# RM-USB.net
KiCad netlist of a schematic drawn in EAGLE
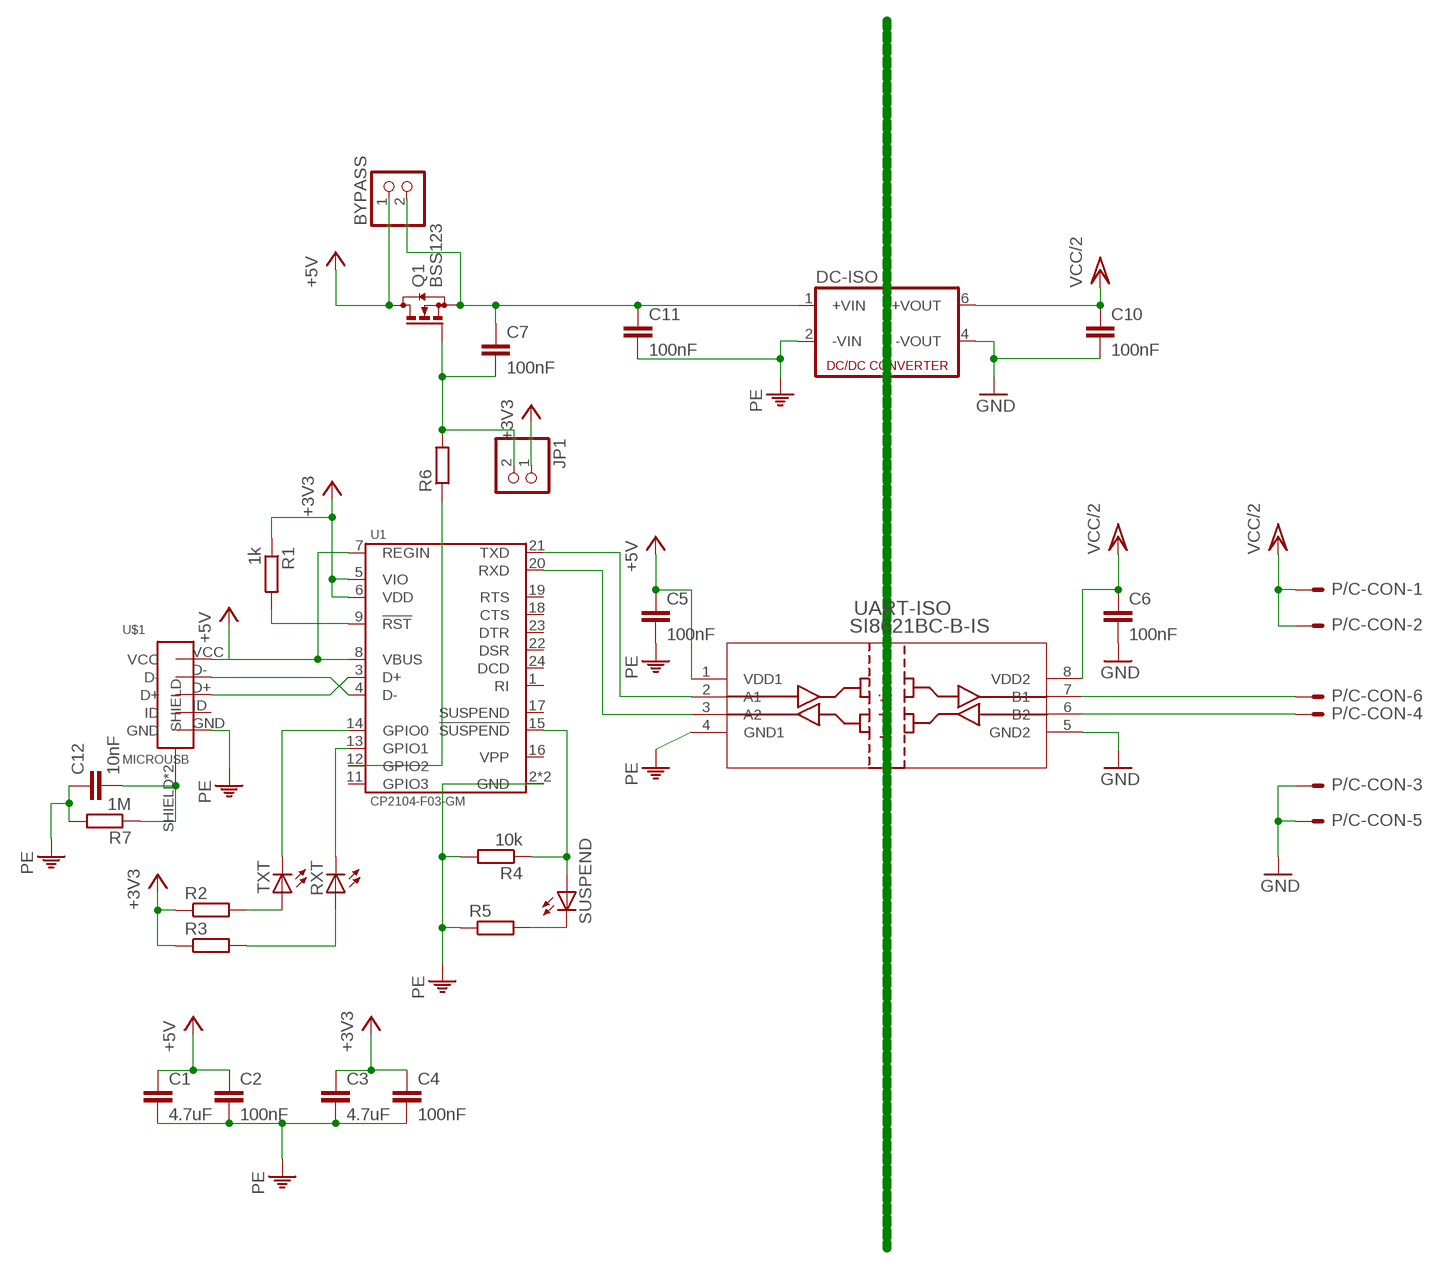
[diagram p0: schematic, sheet 1]

(export (version "E")
  (design (tool "Eeschema 10.0.6"))
  (components
    (comp (ref "BYPASS")
      (value "PINHD-1X2")
      (footprint "eagle-import:1X02")
      (libsource (lib "eagle-import") (part "PINHD-1X2"))
    )
    (comp (ref "C1")
      (value "4.7uF")
      (footprint "eagle-import:C1206K")
      (libsource (lib "eagle-import") (part "C-EUC1206K"))
    )
    (comp (ref "C2")
      (value "100nF")
      (footprint "eagle-import:C0603")
      (libsource (lib "eagle-import") (part "C-EUC0603"))
    )
    (comp (ref "C3")
      (value "4.7uF")
      (footprint "eagle-import:C1206K")
      (libsource (lib "eagle-import") (part "C-EUC1206K"))
    )
    (comp (ref "C4")
      (value "100nF")
      (footprint "eagle-import:C0603")
      (libsource (lib "eagle-import") (part "C-EUC0603"))
    )
    (comp (ref "C5")
      (value "100nF")
      (footprint "eagle-import:C0603")
      (libsource (lib "eagle-import") (part "C-EUC0603"))
    )
    (comp (ref "C6")
      (value "100nF")
      (footprint "eagle-import:C0603")
      (libsource (lib "eagle-import") (part "C-EUC0603"))
    )
    (comp (ref "C7")
      (value "100nF")
      (footprint "eagle-import:C0603")
      (libsource (lib "eagle-import") (part "C-EUC0603"))
    )
    (comp (ref "C10")
      (value "100nF")
      (footprint "eagle-import:C0603")
      (libsource (lib "eagle-import") (part "C-EUC0603"))
    )
    (comp (ref "C11")
      (value "100nF")
      (footprint "eagle-import:C0603")
      (libsource (lib "eagle-import") (part "C-EUC0603"))
    )
    (comp (ref "C12")
      (value "10nF")
      (footprint "eagle-import:C0603")
      (libsource (lib "eagle-import") (part "C-EUC0603"))
    )
    (comp (ref "DC-ISO")
      (value "NMA")
      (footprint "eagle-import:NMA")
      (libsource (lib "eagle-import") (part "NMA"))
    )
    (comp (ref "JP1")
      (value "PINHD-1X2")
      (footprint "eagle-import:1X02")
      (libsource (lib "eagle-import") (part "PINHD-1X2"))
    )
    (comp (ref "P/C-CON")
      (value "ML6EL")
      (footprint "eagle-import:ML6L")
      (libsource (lib "eagle-import") (part "ML6EL"))
    )
    (comp (ref "Q1")
      (value "BSS123")
      (footprint "eagle-import:SOT23")
      (libsource (lib "eagle-import") (part "BSS123"))
    )
    (comp (ref "R1")
      (value "1k")
      (footprint "eagle-import:R0603")
      (libsource (lib "eagle-import") (part "R-EU_R0603"))
    )
    (comp (ref "R2")
      (value "R-EU_R0603")
      (footprint "eagle-import:R0603")
      (libsource (lib "eagle-import") (part "R-EU_R0603"))
    )
    (comp (ref "R3")
      (value "R-EU_R0603")
      (footprint "eagle-import:R0603")
      (libsource (lib "eagle-import") (part "R-EU_R0603"))
    )
    (comp (ref "R4")
      (value "10k")
      (footprint "eagle-import:R0603")
      (libsource (lib "eagle-import") (part "R-EU_R0603"))
    )
    (comp (ref "R5")
      (value "R-EU_R0603")
      (footprint "eagle-import:R0603")
      (libsource (lib "eagle-import") (part "R-EU_R0603"))
    )
    (comp (ref "R6")
      (value "R-EU_R0603")
      (footprint "eagle-import:R0603")
      (libsource (lib "eagle-import") (part "R-EU_R0603"))
    )
    (comp (ref "R7")
      (value "1M")
      (footprint "eagle-import:R0603")
      (libsource (lib "eagle-import") (part "R-EU_R0603"))
    )
    (comp (ref "RXT")
      (value "LED3MM")
      (footprint "eagle-import:LED3MM")
      (libsource (lib "eagle-import") (part "LED3MM"))
    )
    (comp (ref "SUSPEND")
      (value "LED3MM")
      (footprint "eagle-import:LED3MM")
      (libsource (lib "eagle-import") (part "LED3MM"))
    )
    (comp (ref "TXT")
      (value "LED3MM")
      (footprint "eagle-import:LED3MM")
      (libsource (lib "eagle-import") (part "LED3MM"))
    )
    (comp (ref "U$1")
      (value "MICROUSB")
      (footprint "eagle-import:MICROUSB")
      (libsource (lib "eagle-import") (part "MICROUSB"))
    )
    (comp (ref "U1")
      (value "CP2104-F03-GM")
      (footprint "eagle-import:QFN-24-4X4")
      (libsource (lib "eagle-import") (part "CP2104-F03-GM"))
    )
    (comp (ref "UART-ISO")
      (value "SI8621BC-B-IS")
      (footprint "eagle-import:SOIC-8")
      (libsource (lib "eagle-import") (part "SI8621BC-B-IS"))
    )
  )
  (nets
    (net (code "1") (name "+3V3") (class "Default")
      (node (ref "C3") (pin "1") (pinfunction "1_1") (pintype "passive"))
      (node (ref "C4") (pin "1") (pinfunction "1_1") (pintype "passive"))
      (node (ref "JP1") (pin "1") (pinfunction "1_1") (pintype "passive"))
      (node (ref "R1") (pin "1") (pinfunction "1_1") (pintype "passive"))
      (node (ref "R2") (pin "1") (pinfunction "1_1") (pintype "passive"))
      (node (ref "R3") (pin "1") (pinfunction "1_1") (pintype "passive"))
      (node (ref "U1") (pin "5") (pinfunction "VIO_5") (pintype "bidirectional"))
      (node (ref "U1") (pin "6") (pinfunction "VDD_6") (pintype "bidirectional"))
    )
    (net (code "2") (name "+5V") (class "Default")
      (node (ref "BYPASS") (pin "1") (pinfunction "1_1") (pintype "passive"))
      (node (ref "C1") (pin "1") (pinfunction "1_1") (pintype "passive"))
      (node (ref "C2") (pin "1") (pinfunction "1_1") (pintype "passive"))
      (node (ref "C5") (pin "1") (pinfunction "1_1") (pintype "passive"))
      (node (ref "Q1") (pin "3") (pinfunction "D_3") (pintype "passive"))
      (node (ref "U$1") (pin "VCC") (pinfunction "VCC_VCC") (pintype "bidirectional"))
      (node (ref "U1") (pin "7") (pinfunction "REGIN_7") (pintype "bidirectional"))
      (node (ref "U1") (pin "8") (pinfunction "VBUS_8") (pintype "bidirectional"))
      (node (ref "UART-ISO") (pin "1") (pinfunction "VDD1_1") (pintype "passive"))
    )
    (net (code "3") (name "GND") (class "Default")
      (node (ref "C10") (pin "2") (pinfunction "2_2") (pintype "passive"))
      (node (ref "C6") (pin "2") (pinfunction "2_2") (pintype "passive"))
      (node (ref "DC-ISO") (pin "4") (pinfunction "-VOUT_4") (pintype "passive"))
      (node (ref "P/C-CON") (pin "3") (pinfunction "S_3") (pintype "passive"))
      (node (ref "P/C-CON") (pin "5") (pinfunction "S_5") (pintype "passive"))
      (node (ref "UART-ISO") (pin "5") (pinfunction "GND2_5") (pintype "passive"))
    )
    (net (code "4") (name "Net-(C12-Pad2)") (class "Default")
      (node (ref "C12") (pin "2") (pinfunction "2_2") (pintype "passive"))
      (node (ref "R7") (pin "1") (pinfunction "1_1") (pintype "passive"))
      (node (ref "U$1") (pin "SHIELD") (pinfunction "SHIELD_SHIELD") (pintype "bidirectional"))
      (node (ref "U$1") (pin "SHIELD1") (pinfunction "SHIELD_SHIELD1") (pintype "bidirectional"))
    )
    (net (code "5") (name "Net-(DC-ISO-+VIN)") (class "Default")
      (node (ref "BYPASS") (pin "2") (pinfunction "2_2") (pintype "passive"))
      (node (ref "C11") (pin "1") (pinfunction "1_1") (pintype "passive"))
      (node (ref "C7") (pin "1") (pinfunction "1_1") (pintype "passive"))
      (node (ref "DC-ISO") (pin "1") (pinfunction "+VIN_1") (pintype "passive"))
      (node (ref "Q1") (pin "2") (pinfunction "S_2") (pintype "passive"))
    )
    (net (code "6") (name "Net-(P/C-COND-S)") (class "Default")
      (node (ref "P/C-CON") (pin "4") (pinfunction "S_4") (pintype "passive"))
      (node (ref "UART-ISO") (pin "6") (pinfunction "B2_6") (pintype "input"))
    )
    (net (code "7") (name "Net-(P/C-CONF-S)") (class "Default")
      (node (ref "P/C-CON") (pin "6") (pinfunction "S_6") (pintype "passive"))
      (node (ref "UART-ISO") (pin "7") (pinfunction "B1_7") (pintype "output"))
    )
    (net (code "8") (name "Net-(Q1-G)") (class "Default")
      (node (ref "C7") (pin "2") (pinfunction "2_2") (pintype "passive"))
      (node (ref "JP1") (pin "2") (pinfunction "2_2") (pintype "passive"))
      (node (ref "Q1") (pin "1") (pinfunction "G_1") (pintype "passive"))
      (node (ref "R6") (pin "2") (pinfunction "2_2") (pintype "passive"))
    )
    (net (code "9") (name "Net-(R2-Pad2)") (class "Default")
      (node (ref "R2") (pin "2") (pinfunction "2_2") (pintype "passive"))
      (node (ref "TXT") (pin "A") (pinfunction "A_A") (pintype "passive"))
    )
    (net (code "10") (name "Net-(R3-Pad2)") (class "Default")
      (node (ref "R3") (pin "2") (pinfunction "2_2") (pintype "passive"))
      (node (ref "RXT") (pin "A") (pinfunction "A_A") (pintype "passive"))
    )
    (net (code "11") (name "Net-(RXT-C)") (class "Default")
      (node (ref "RXT") (pin "K") (pinfunction "C_K") (pintype "passive"))
      (node (ref "U1") (pin "13") (pinfunction "GPIO1_13") (pintype "bidirectional"))
    )
    (net (code "12") (name "Net-(SUSPEND-C)") (class "Default")
      (node (ref "R5") (pin "2") (pinfunction "2_2") (pintype "passive"))
      (node (ref "SUSPEND") (pin "K") (pinfunction "C_K") (pintype "passive"))
    )
    (net (code "13") (name "Net-(TXT-C)") (class "Default")
      (node (ref "TXT") (pin "K") (pinfunction "C_K") (pintype "passive"))
      (node (ref "U1") (pin "14") (pinfunction "GPIO0_14") (pintype "bidirectional"))
    )
    (net (code "14") (name "Net-(U1-D+)") (class "Default")
      (node (ref "U$1") (pin "D+") (pinfunction "D+_D+") (pintype "bidirectional"))
      (node (ref "U1") (pin "3") (pinfunction "D+_3") (pintype "bidirectional"))
    )
    (net (code "15") (name "Net-(U1-D-)") (class "Default")
      (node (ref "U$1") (pin "D-") (pinfunction "D-_D-") (pintype "bidirectional"))
      (node (ref "U1") (pin "4") (pinfunction "D-_4") (pintype "bidirectional"))
    )
    (net (code "16") (name "Net-(U1-GPIO2)") (class "Default")
      (node (ref "R6") (pin "1") (pinfunction "1_1") (pintype "passive"))
      (node (ref "U1") (pin "12") (pinfunction "GPIO2_12") (pintype "bidirectional"))
    )
    (net (code "17") (name "Net-(U1-RXD)") (class "Default")
      (node (ref "U1") (pin "20") (pinfunction "RXD_20") (pintype "bidirectional"))
      (node (ref "UART-ISO") (pin "3") (pinfunction "A2_3") (pintype "output"))
    )
    (net (code "18") (name "Net-(U1-TXD)") (class "Default")
      (node (ref "U1") (pin "21") (pinfunction "TXD_21") (pintype "bidirectional"))
      (node (ref "UART-ISO") (pin "2") (pinfunction "A1_2") (pintype "input"))
    )
    (net (code "19") (name "Net-(U1-~{RST})") (class "Default")
      (node (ref "R1") (pin "2") (pinfunction "2_2") (pintype "passive"))
      (node (ref "U1") (pin "9") (pinfunction "~{RST}_9") (pintype "bidirectional"))
    )
    (net (code "20") (name "Net-(U1-~{SUSPEND})") (class "Default")
      (node (ref "R4") (pin "1") (pinfunction "1_1") (pintype "passive"))
      (node (ref "SUSPEND") (pin "A") (pinfunction "A_A") (pintype "passive"))
      (node (ref "U1") (pin "15") (pinfunction "~{SUSPEND}_15") (pintype "bidirectional"))
    )
    (net (code "21") (name "PE") (class "Default")
      (node (ref "C1") (pin "2") (pinfunction "2_2") (pintype "passive"))
      (node (ref "C11") (pin "2") (pinfunction "2_2") (pintype "passive"))
      (node (ref "C12") (pin "1") (pinfunction "1_1") (pintype "passive"))
      (node (ref "C2") (pin "2") (pinfunction "2_2") (pintype "passive"))
      (node (ref "C3") (pin "2") (pinfunction "2_2") (pintype "passive"))
      (node (ref "C4") (pin "2") (pinfunction "2_2") (pintype "passive"))
      (node (ref "C5") (pin "2") (pinfunction "2_2") (pintype "passive"))
      (node (ref "DC-ISO") (pin "2") (pinfunction "-VIN_2") (pintype "passive"))
      (node (ref "R4") (pin "2") (pinfunction "2_2") (pintype "passive"))
      (node (ref "R5") (pin "1") (pinfunction "1_1") (pintype "passive"))
      (node (ref "R7") (pin "2") (pinfunction "2_2") (pintype "passive"))
      (node (ref "U$1") (pin "GND") (pinfunction "GND_GND") (pintype "bidirectional"))
      (node (ref "U1") (pin "2") (pinfunction "GND_2") (pintype "bidirectional"))
      (node (ref "U1") (pin "PAD") (pinfunction "GND_PAD") (pintype "bidirectional"))
      (node (ref "UART-ISO") (pin "4") (pinfunction "GND1_4") (pintype "passive"))
    )
    (net (code "22") (name "VCC{slash}2") (class "Default")
      (node (ref "C10") (pin "1") (pinfunction "1_1") (pintype "passive"))
      (node (ref "C6") (pin "1") (pinfunction "1_1") (pintype "passive"))
      (node (ref "DC-ISO") (pin "6") (pinfunction "+VOUT_6") (pintype "passive"))
      (node (ref "P/C-CON") (pin "1") (pinfunction "S_1") (pintype "passive"))
      (node (ref "P/C-CON") (pin "2") (pinfunction "S_2") (pintype "passive"))
      (node (ref "UART-ISO") (pin "8") (pinfunction "VDD2_8") (pintype "passive"))
    )
    (net (code "23") (name "unconnected-(U$1-PadID)") (class "Default")
      (node (ref "U$1") (pin "ID") (pinfunction "ID_ID") (pintype "bidirectional"))
    )
    (net (code "24") (name "unconnected-(U1-CTS-Pad18)") (class "Default")
      (node (ref "U1") (pin "18") (pinfunction "CTS_18") (pintype "bidirectional"))
    )
    (net (code "25") (name "unconnected-(U1-DCD-Pad24)") (class "Default")
      (node (ref "U1") (pin "24") (pinfunction "DCD_24") (pintype "bidirectional"))
    )
    (net (code "26") (name "unconnected-(U1-DSR-Pad22)") (class "Default")
      (node (ref "U1") (pin "22") (pinfunction "DSR_22") (pintype "bidirectional"))
    )
    (net (code "27") (name "unconnected-(U1-DTR-Pad23)") (class "Default")
      (node (ref "U1") (pin "23") (pinfunction "DTR_23") (pintype "bidirectional"))
    )
    (net (code "28") (name "unconnected-(U1-GPIO3-Pad11)") (class "Default")
      (node (ref "U1") (pin "11") (pinfunction "GPIO3_11") (pintype "bidirectional"))
    )
    (net (code "29") (name "unconnected-(U1-RI-Pad1)") (class "Default")
      (node (ref "U1") (pin "1") (pinfunction "RI_1") (pintype "bidirectional"))
    )
    (net (code "30") (name "unconnected-(U1-RTS-Pad19)") (class "Default")
      (node (ref "U1") (pin "19") (pinfunction "RTS_19") (pintype "bidirectional"))
    )
    (net (code "31") (name "unconnected-(U1-SUSPEND-Pad17)") (class "Default")
      (node (ref "U1") (pin "17") (pinfunction "SUSPEND_17") (pintype "bidirectional"))
    )
    (net (code "32") (name "unconnected-(U1-VPP-Pad16)") (class "Default")
      (node (ref "U1") (pin "16") (pinfunction "VPP_16") (pintype "bidirectional"))
    )
  )
)
